# ALU_AND.net
KiCad netlist of a schematic drawn in Altium Designer
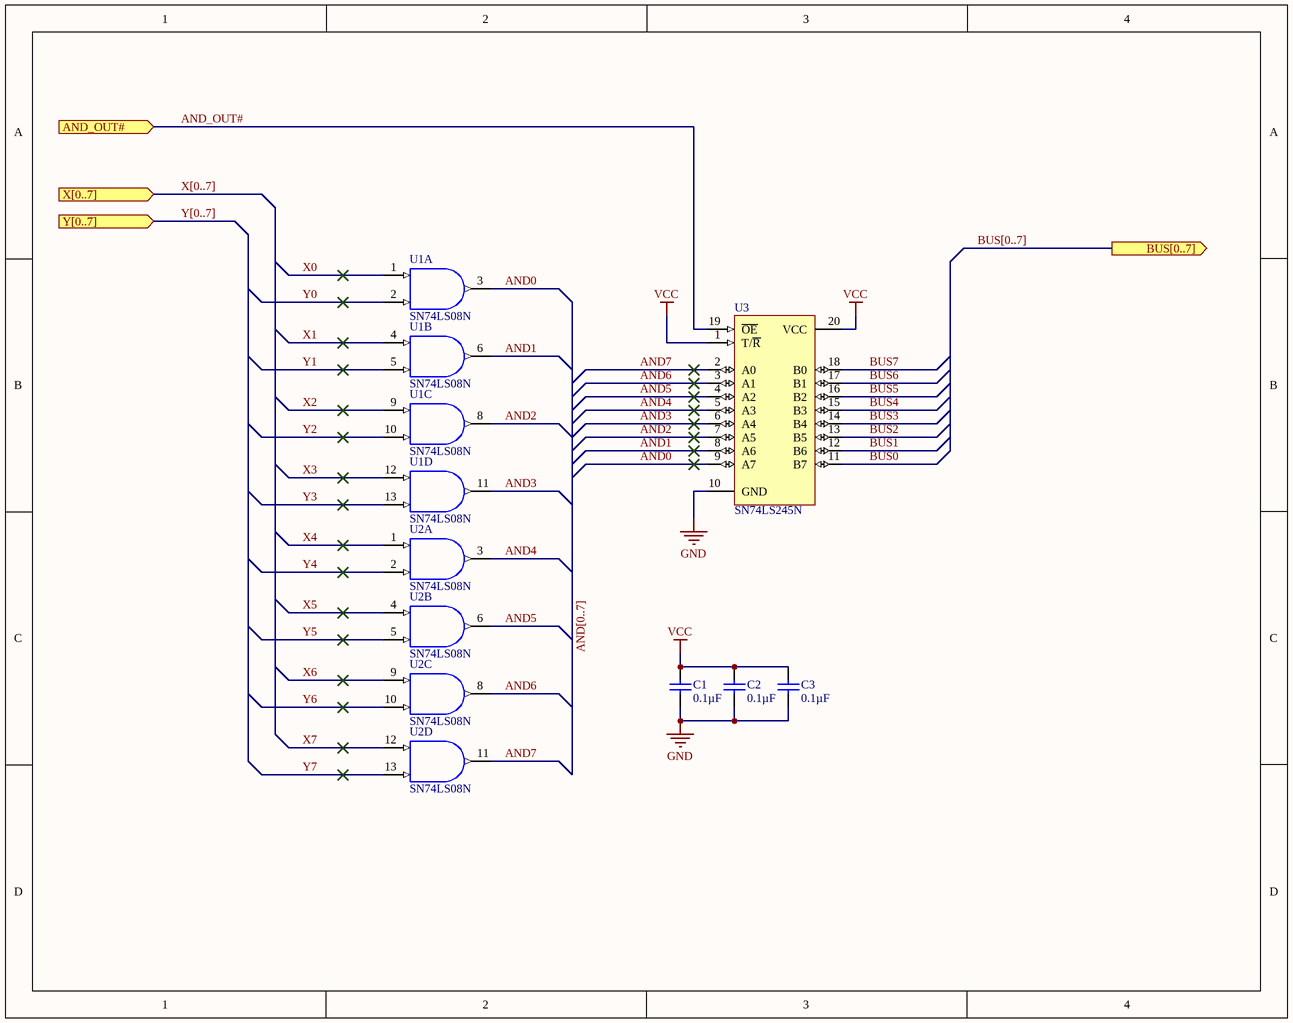
[diagram p0: ALU_AND.SchDoc]

(export (version "E")
  (design (tool "Eeschema 10.0.6"))
  (components
    (comp (ref "C1")
      (value "K104K15X7RF5TL2")
      (footprint "VISH-K104K15X7RF5TL2")
      (description "Ceramic Capacitor, 100 nF, +/- 10%, 50 V, -55 to 125 degC, 2-Pin THD, RoHS, Tape and Reel")
      (fields
        (field (name "MANUFACTURER") "Vishay")
        (field (name "TOLERANCE") "±10%")
        (field (name "CAPACITANCE") "0.1µF")
      )
      (libsource (lib "Altium Content Vault") (part "CAP-NP-2"))
    )
    (comp (ref "C2")
      (value "K104K15X7RF5TL2")
      (footprint "VISH-K104K15X7RF5TL2")
      (description "Ceramic Capacitor, 100 nF, +/- 10%, 50 V, -55 to 125 degC, 2-Pin THD, RoHS, Tape and Reel")
      (fields
        (field (name "MANUFACTURER") "Vishay")
        (field (name "TOLERANCE") "±10%")
        (field (name "CAPACITANCE") "0.1µF")
      )
      (libsource (lib "Altium Content Vault") (part "CAP-NP-2"))
    )
    (comp (ref "C3")
      (value "K104K15X7RF5TL2")
      (footprint "VISH-K104K15X7RF5TL2")
      (description "Ceramic Capacitor, 100 nF, +/- 10%, 50 V, -55 to 125 degC, 2-Pin THD, RoHS, Tape and Reel")
      (fields
        (field (name "MANUFACTURER") "Vishay")
        (field (name "TOLERANCE") "±10%")
        (field (name "CAPACITANCE") "0.1µF")
      )
      (libsource (lib "Altium Content Vault") (part "CAP-NP-2"))
    )
    (comp (ref "U1")
      (value "SN74LS08N")
      (footprint "N014")
      (description "Quadruple 2-Input Positive-AND Gate")
      (fields (field (name "PUBLISHER") "Altium Limited"))
      (libsource (lib "TI Logic Gate 2") (part "SN74LS08N"))
    )
    (comp (ref "U2")
      (value "SN74LS08N")
      (footprint "N014")
      (description "Quadruple 2-Input Positive-AND Gate")
      (fields (field (name "PUBLISHER") "Altium Limited"))
      (libsource (lib "TI Logic Gate 2") (part "SN74LS08N"))
    )
    (comp (ref "U3")
      (value "SN74LS245N")
      (footprint "N020")
      (description "Octal Bus Transceiver with 3-State Outputs")
      (fields (field (name "PUBLISHER") "Altium Limited"))
      (libsource (lib "TI Interface 8-Bit Line Transceiver") (part "SN74LS245N"))
    )
  )
  (nets
    (net (code "1") (name "/AND0") (class "Default")
      (node (ref "U1") (pin "3") (pinfunction "Y_3") (pintype "output"))
      (node (ref "U3") (pin "9") (pinfunction "A7_9") (pintype "bidirectional"))
    )
    (net (code "2") (name "/AND1") (class "Default")
      (node (ref "U1") (pin "6") (pinfunction "Y_6") (pintype "output"))
      (node (ref "U3") (pin "8") (pinfunction "A6_8") (pintype "bidirectional"))
    )
    (net (code "3") (name "/AND2") (class "Default")
      (node (ref "U1") (pin "8") (pinfunction "Y_8") (pintype "output"))
      (node (ref "U3") (pin "7") (pinfunction "A5_7") (pintype "bidirectional"))
    )
    (net (code "4") (name "/AND3") (class "Default")
      (node (ref "U1") (pin "11") (pinfunction "Y_11") (pintype "output"))
      (node (ref "U3") (pin "6") (pinfunction "A4_6") (pintype "bidirectional"))
    )
    (net (code "5") (name "/AND4") (class "Default")
      (node (ref "U2") (pin "3") (pinfunction "Y_3") (pintype "output"))
      (node (ref "U3") (pin "5") (pinfunction "A3_5") (pintype "bidirectional"))
    )
    (net (code "6") (name "/AND5") (class "Default")
      (node (ref "U2") (pin "6") (pinfunction "Y_6") (pintype "output"))
      (node (ref "U3") (pin "4") (pinfunction "A2_4") (pintype "bidirectional"))
    )
    (net (code "7") (name "/AND6") (class "Default")
      (node (ref "U2") (pin "8") (pinfunction "Y_8") (pintype "output"))
      (node (ref "U3") (pin "3") (pinfunction "A1_3") (pintype "bidirectional"))
    )
    (net (code "8") (name "/AND7") (class "Default")
      (node (ref "U2") (pin "11") (pinfunction "Y_11") (pintype "output"))
      (node (ref "U3") (pin "2") (pinfunction "A0_2") (pintype "bidirectional"))
    )
    (net (code "10") (name "/AND_OUT#") (class "Default")
      (node (ref "U3") (pin "19") (pinfunction "~{OE}_19") (pintype "input"))
    )
    (net (code "11") (name "/BUS0") (class "Default")
      (node (ref "U3") (pin "11") (pinfunction "B7_11") (pintype "bidirectional"))
    )
    (net (code "12") (name "/BUS1") (class "Default")
      (node (ref "U3") (pin "12") (pinfunction "B6_12") (pintype "bidirectional"))
    )
    (net (code "13") (name "/BUS2") (class "Default")
      (node (ref "U3") (pin "13") (pinfunction "B5_13") (pintype "bidirectional"))
    )
    (net (code "14") (name "/BUS3") (class "Default")
      (node (ref "U3") (pin "14") (pinfunction "B4_14") (pintype "bidirectional"))
    )
    (net (code "15") (name "/BUS4") (class "Default")
      (node (ref "U3") (pin "15") (pinfunction "B3_15") (pintype "bidirectional"))
    )
    (net (code "16") (name "/BUS5") (class "Default")
      (node (ref "U3") (pin "16") (pinfunction "B2_16") (pintype "bidirectional"))
    )
    (net (code "17") (name "/BUS6") (class "Default")
      (node (ref "U3") (pin "17") (pinfunction "B1_17") (pintype "bidirectional"))
    )
    (net (code "18") (name "/BUS7") (class "Default")
      (node (ref "U3") (pin "18") (pinfunction "B0_18") (pintype "bidirectional"))
    )
    (net (code "20") (name "/X0") (class "Default")
      (node (ref "U1") (pin "1") (pinfunction "A_1") (pintype "input"))
    )
    (net (code "21") (name "/X1") (class "Default")
      (node (ref "U1") (pin "4") (pinfunction "A_4") (pintype "input"))
    )
    (net (code "22") (name "/X2") (class "Default")
      (node (ref "U1") (pin "9") (pinfunction "A_9") (pintype "input"))
    )
    (net (code "23") (name "/X3") (class "Default")
      (node (ref "U1") (pin "12") (pinfunction "A_12") (pintype "input"))
    )
    (net (code "24") (name "/X4") (class "Default")
      (node (ref "U2") (pin "1") (pinfunction "A_1") (pintype "input"))
    )
    (net (code "25") (name "/X5") (class "Default")
      (node (ref "U2") (pin "4") (pinfunction "A_4") (pintype "input"))
    )
    (net (code "26") (name "/X6") (class "Default")
      (node (ref "U2") (pin "9") (pinfunction "A_9") (pintype "input"))
    )
    (net (code "27") (name "/X7") (class "Default")
      (node (ref "U2") (pin "12") (pinfunction "A_12") (pintype "input"))
    )
    (net (code "29") (name "/Y0") (class "Default")
      (node (ref "U1") (pin "2") (pinfunction "B_2") (pintype "input"))
    )
    (net (code "30") (name "/Y1") (class "Default")
      (node (ref "U1") (pin "5") (pinfunction "B_5") (pintype "input"))
    )
    (net (code "31") (name "/Y2") (class "Default")
      (node (ref "U1") (pin "10") (pinfunction "B_10") (pintype "input"))
    )
    (net (code "32") (name "/Y3") (class "Default")
      (node (ref "U1") (pin "13") (pinfunction "B_13") (pintype "input"))
    )
    (net (code "33") (name "/Y4") (class "Default")
      (node (ref "U2") (pin "2") (pinfunction "B_2") (pintype "input"))
    )
    (net (code "34") (name "/Y5") (class "Default")
      (node (ref "U2") (pin "5") (pinfunction "B_5") (pintype "input"))
    )
    (net (code "35") (name "/Y6") (class "Default")
      (node (ref "U2") (pin "10") (pinfunction "B_10") (pintype "input"))
    )
    (net (code "36") (name "/Y7") (class "Default")
      (node (ref "U2") (pin "13") (pinfunction "B_13") (pintype "input"))
    )
    (net (code "38") (name "GND") (class "Default")
      (node (ref "C1") (pin "2") (pinfunction "2_2") (pintype "passive"))
      (node (ref "C2") (pin "2") (pinfunction "2_2") (pintype "passive"))
      (node (ref "C3") (pin "2") (pinfunction "2_2") (pintype "passive"))
      (node (ref "U1") (pin "7") (pinfunction "GND_7") (pintype "power_in"))
      (node (ref "U2") (pin "7") (pinfunction "GND_7") (pintype "power_in"))
      (node (ref "U3") (pin "10") (pinfunction "GND_10") (pintype "power_in"))
    )
    (net (code "39") (name "VCC") (class "Default")
      (node (ref "C1") (pin "1") (pinfunction "1_1") (pintype "passive"))
      (node (ref "C2") (pin "1") (pinfunction "1_1") (pintype "passive"))
      (node (ref "C3") (pin "1") (pinfunction "1_1") (pintype "passive"))
      (node (ref "U1") (pin "14") (pinfunction "VCC_14") (pintype "power_in"))
      (node (ref "U2") (pin "14") (pinfunction "VCC_14") (pintype "power_in"))
      (node (ref "U3") (pin "1") (pinfunction "T/~{R}_1") (pintype "input"))
      (node (ref "U3") (pin "20") (pinfunction "VCC_20") (pintype "power_in"))
    )
  )
)
